# KissCart64-8K-DIP.net
KiCad netlist of a schematic drawn in EAGLE
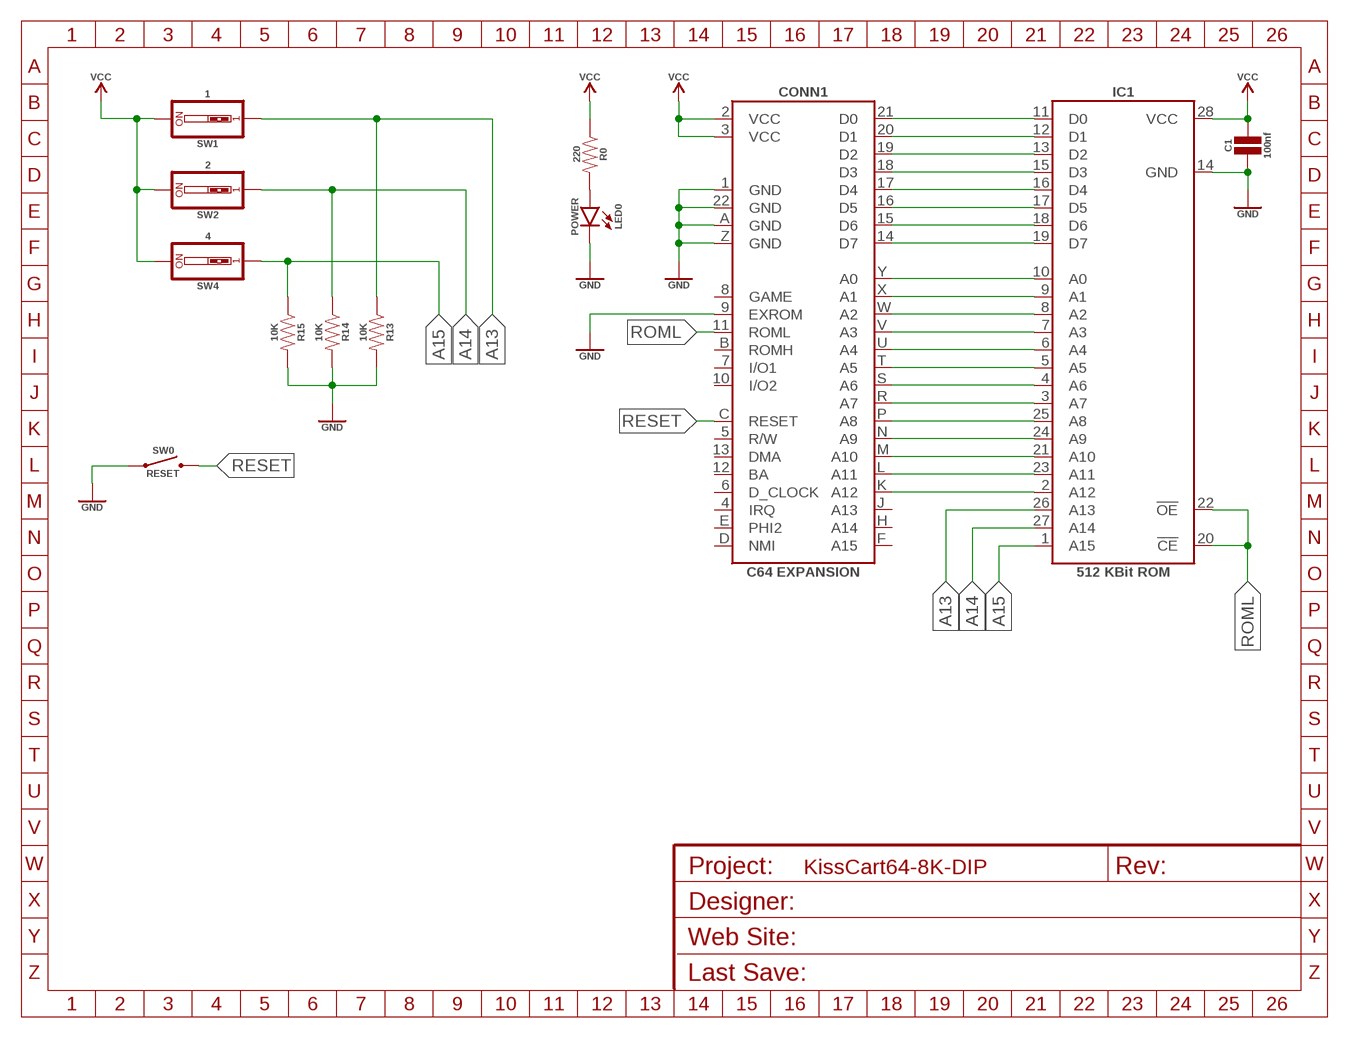
[diagram p0: schematic, sheet 1]

(export (version "E")
  (design (tool "Eeschema 10.0.6"))
  (components
    (comp (ref "C1")
      (value "100nf")
      (footprint "eagle-import:CAPACITOR_CERAMIC_0.2")
      (libsource (lib "eagle-import") (part "CAPACITOR_CERAMIC_0.2"))
    )
    (comp (ref "CONN1")
      (value "C64 EXPANSION")
      (footprint "eagle-import:C64_CARTRIDGE")
      (libsource (lib "eagle-import") (part "C64_CARTDRIGE"))
    )
    (comp (ref "IC1")
      (value "512 KBit ROM")
      (footprint "eagle-import:DIP28W")
      (libsource (lib "eagle-import") (part "27C512_DIP"))
    )
    (comp (ref "LED0")
      (value "POWER")
      (footprint "eagle-import:LED_1206")
      (libsource (lib "eagle-import") (part "LED_NORMAL_1206"))
    )
    (comp (ref "R0")
      (value "220")
      (footprint "eagle-import:RESISTOR_SMT_1206")
      (libsource (lib "eagle-import") (part "RESISTOR_SMT_1206"))
    )
    (comp (ref "R13")
      (value "10K")
      (footprint "eagle-import:RESISTOR_SMT_1206")
      (libsource (lib "eagle-import") (part "RESISTOR_SMT_1206"))
    )
    (comp (ref "R14")
      (value "10K")
      (footprint "eagle-import:RESISTOR_SMT_1206")
      (libsource (lib "eagle-import") (part "RESISTOR_SMT_1206"))
    )
    (comp (ref "R15")
      (value "10K")
      (footprint "eagle-import:RESISTOR_SMT_1206")
      (libsource (lib "eagle-import") (part "RESISTOR_SMT_1206"))
    )
    (comp (ref "SW0")
      (value "RESET")
      (footprint "eagle-import:SWITCH_THT_SIDE")
      (libsource (lib "eagle-import") (part "SWITCH_THT_SIDE"))
    )
    (comp (ref "SW1")
      (value "1")
      (footprint "eagle-import:SWITCH_DIP_01")
      (libsource (lib "eagle-import") (part "SWITCH_DIP_01"))
    )
    (comp (ref "SW2")
      (value "2")
      (footprint "eagle-import:SWITCH_DIP_01")
      (libsource (lib "eagle-import") (part "SWITCH_DIP_01"))
    )
    (comp (ref "SW4")
      (value "4")
      (footprint "eagle-import:SWITCH_DIP_01")
      (libsource (lib "eagle-import") (part "SWITCH_DIP_01"))
    )
  )
  (nets
    (net (code "1") (name "A13") (class "Default")
      (node (ref "IC1") (pin "26") (pinfunction "A13_26") (pintype "input"))
      (node (ref "R13") (pin "1") (pinfunction "1_1") (pintype "passive"))
      (node (ref "SW1") (pin "1") (pinfunction "1_1") (pintype "passive"))
    )
    (net (code "2") (name "A14") (class "Default")
      (node (ref "IC1") (pin "27") (pinfunction "A14_27") (pintype "input"))
      (node (ref "R14") (pin "1") (pinfunction "1_1") (pintype "passive"))
      (node (ref "SW2") (pin "1") (pinfunction "1_1") (pintype "passive"))
    )
    (net (code "3") (name "A15") (class "Default")
      (node (ref "IC1") (pin "1") (pinfunction "A15_1") (pintype "input"))
      (node (ref "R15") (pin "1") (pinfunction "1_1") (pintype "passive"))
      (node (ref "SW4") (pin "1") (pinfunction "1_1") (pintype "passive"))
    )
    (net (code "4") (name "GND") (class "Default")
      (node (ref "C1") (pin "1") (pinfunction "1_1") (pintype "passive"))
      (node (ref "CONN1") (pin "1") (pinfunction "GND_1") (pintype "bidirectional"))
      (node (ref "CONN1") (pin "22") (pinfunction "GND_22") (pintype "bidirectional"))
      (node (ref "CONN1") (pin "9") (pinfunction "EXROM_9") (pintype "bidirectional"))
      (node (ref "CONN1") (pin "A") (pinfunction "GND_A") (pintype "bidirectional"))
      (node (ref "CONN1") (pin "Z") (pinfunction "GND_Z") (pintype "bidirectional"))
      (node (ref "IC1") (pin "14") (pinfunction "GND_14") (pintype "power_in"))
      (node (ref "LED0") (pin "C") (pinfunction "C_C") (pintype "passive"))
      (node (ref "R13") (pin "2") (pinfunction "2_2") (pintype "passive"))
      (node (ref "R14") (pin "2") (pinfunction "2_2") (pintype "passive"))
      (node (ref "R15") (pin "2") (pinfunction "2_2") (pintype "passive"))
      (node (ref "SW0") (pin "1") (pinfunction "1_1") (pintype "passive"))
    )
    (net (code "5") (name "Net-(CONN1-A0)") (class "Default")
      (node (ref "CONN1") (pin "Y") (pinfunction "A0_Y") (pintype "bidirectional"))
      (node (ref "IC1") (pin "10") (pinfunction "A0_10") (pintype "input"))
    )
    (net (code "6") (name "Net-(CONN1-A1)") (class "Default")
      (node (ref "CONN1") (pin "X") (pinfunction "A1_X") (pintype "bidirectional"))
      (node (ref "IC1") (pin "9") (pinfunction "A1_9") (pintype "input"))
    )
    (net (code "7") (name "Net-(CONN1-A2)") (class "Default")
      (node (ref "CONN1") (pin "W") (pinfunction "A2_W") (pintype "bidirectional"))
      (node (ref "IC1") (pin "8") (pinfunction "A2_8") (pintype "input"))
    )
    (net (code "8") (name "Net-(CONN1-A3)") (class "Default")
      (node (ref "CONN1") (pin "V") (pinfunction "A3_V") (pintype "bidirectional"))
      (node (ref "IC1") (pin "7") (pinfunction "A3_7") (pintype "input"))
    )
    (net (code "9") (name "Net-(CONN1-A4)") (class "Default")
      (node (ref "CONN1") (pin "U") (pinfunction "A4_U") (pintype "bidirectional"))
      (node (ref "IC1") (pin "6") (pinfunction "A4_6") (pintype "input"))
    )
    (net (code "10") (name "Net-(CONN1-A5)") (class "Default")
      (node (ref "CONN1") (pin "T") (pinfunction "A5_T") (pintype "bidirectional"))
      (node (ref "IC1") (pin "5") (pinfunction "A5_5") (pintype "input"))
    )
    (net (code "11") (name "Net-(CONN1-A6)") (class "Default")
      (node (ref "CONN1") (pin "S") (pinfunction "A6_S") (pintype "bidirectional"))
      (node (ref "IC1") (pin "4") (pinfunction "A6_4") (pintype "input"))
    )
    (net (code "12") (name "Net-(CONN1-A7)") (class "Default")
      (node (ref "CONN1") (pin "R") (pinfunction "A7_R") (pintype "bidirectional"))
      (node (ref "IC1") (pin "3") (pinfunction "A7_3") (pintype "input"))
    )
    (net (code "13") (name "Net-(CONN1-A8)") (class "Default")
      (node (ref "CONN1") (pin "P") (pinfunction "A8_P") (pintype "bidirectional"))
      (node (ref "IC1") (pin "25") (pinfunction "A8_25") (pintype "input"))
    )
    (net (code "14") (name "Net-(CONN1-A9)") (class "Default")
      (node (ref "CONN1") (pin "N") (pinfunction "A9_N") (pintype "bidirectional"))
      (node (ref "IC1") (pin "24") (pinfunction "A9_24") (pintype "input"))
    )
    (net (code "15") (name "Net-(CONN1-A10)") (class "Default")
      (node (ref "CONN1") (pin "M") (pinfunction "A10_M") (pintype "bidirectional"))
      (node (ref "IC1") (pin "21") (pinfunction "A10_21") (pintype "input"))
    )
    (net (code "16") (name "Net-(CONN1-A11)") (class "Default")
      (node (ref "CONN1") (pin "L") (pinfunction "A11_L") (pintype "bidirectional"))
      (node (ref "IC1") (pin "23") (pinfunction "A11_23") (pintype "input"))
    )
    (net (code "17") (name "Net-(CONN1-A12)") (class "Default")
      (node (ref "CONN1") (pin "K") (pinfunction "A12_K") (pintype "bidirectional"))
      (node (ref "IC1") (pin "2") (pinfunction "A12_2") (pintype "input"))
    )
    (net (code "18") (name "Net-(CONN1-D0)") (class "Default")
      (node (ref "CONN1") (pin "21") (pinfunction "D0_21") (pintype "bidirectional"))
      (node (ref "IC1") (pin "11") (pinfunction "D0_11") (pintype "tri_state"))
    )
    (net (code "19") (name "Net-(CONN1-D1)") (class "Default")
      (node (ref "CONN1") (pin "20") (pinfunction "D1_20") (pintype "bidirectional"))
      (node (ref "IC1") (pin "12") (pinfunction "D1_12") (pintype "tri_state"))
    )
    (net (code "20") (name "Net-(CONN1-D2)") (class "Default")
      (node (ref "CONN1") (pin "19") (pinfunction "D2_19") (pintype "bidirectional"))
      (node (ref "IC1") (pin "13") (pinfunction "D2_13") (pintype "tri_state"))
    )
    (net (code "21") (name "Net-(CONN1-D3)") (class "Default")
      (node (ref "CONN1") (pin "18") (pinfunction "D3_18") (pintype "bidirectional"))
      (node (ref "IC1") (pin "15") (pinfunction "D3_15") (pintype "tri_state"))
    )
    (net (code "22") (name "Net-(CONN1-D4)") (class "Default")
      (node (ref "CONN1") (pin "17") (pinfunction "D4_17") (pintype "bidirectional"))
      (node (ref "IC1") (pin "16") (pinfunction "D4_16") (pintype "tri_state"))
    )
    (net (code "23") (name "Net-(CONN1-D5)") (class "Default")
      (node (ref "CONN1") (pin "16") (pinfunction "D5_16") (pintype "bidirectional"))
      (node (ref "IC1") (pin "17") (pinfunction "D5_17") (pintype "tri_state"))
    )
    (net (code "24") (name "Net-(CONN1-D6)") (class "Default")
      (node (ref "CONN1") (pin "15") (pinfunction "D6_15") (pintype "bidirectional"))
      (node (ref "IC1") (pin "18") (pinfunction "D6_18") (pintype "tri_state"))
    )
    (net (code "25") (name "Net-(CONN1-D7)") (class "Default")
      (node (ref "CONN1") (pin "14") (pinfunction "D7_14") (pintype "bidirectional"))
      (node (ref "IC1") (pin "19") (pinfunction "D7_19") (pintype "tri_state"))
    )
    (net (code "26") (name "Net-(LED0-PadA)") (class "Default")
      (node (ref "LED0") (pin "A") (pinfunction "A_A") (pintype "passive"))
      (node (ref "R0") (pin "2") (pinfunction "2_2") (pintype "passive"))
    )
    (net (code "27") (name "RESET") (class "Default")
      (node (ref "CONN1") (pin "C") (pinfunction "RESET_C") (pintype "bidirectional"))
      (node (ref "SW0") (pin "2") (pinfunction "2_2") (pintype "passive"))
    )
    (net (code "28") (name "ROML") (class "Default")
      (node (ref "CONN1") (pin "11") (pinfunction "ROML_11") (pintype "bidirectional"))
      (node (ref "IC1") (pin "20") (pinfunction "~{CE}_20") (pintype "input"))
      (node (ref "IC1") (pin "22") (pinfunction "~{OE}_22") (pintype "input"))
    )
    (net (code "29") (name "VCC") (class "Default")
      (node (ref "C1") (pin "2") (pinfunction "2_2") (pintype "passive"))
      (node (ref "CONN1") (pin "2") (pinfunction "VCC_2") (pintype "bidirectional"))
      (node (ref "CONN1") (pin "3") (pinfunction "VCC_3") (pintype "bidirectional"))
      (node (ref "IC1") (pin "28") (pinfunction "VCC_28") (pintype "power_in"))
      (node (ref "R0") (pin "1") (pinfunction "1_1") (pintype "passive"))
      (node (ref "SW1") (pin "2") (pinfunction "2_2") (pintype "passive"))
      (node (ref "SW2") (pin "2") (pinfunction "2_2") (pintype "passive"))
      (node (ref "SW4") (pin "2") (pinfunction "2_2") (pintype "passive"))
    )
    (net (code "30") (name "unconnected-(CONN1-A13-PadJ)") (class "Default")
      (node (ref "CONN1") (pin "J") (pinfunction "A13_J") (pintype "bidirectional"))
    )
    (net (code "31") (name "unconnected-(CONN1-A14-PadH)") (class "Default")
      (node (ref "CONN1") (pin "H") (pinfunction "A14_H") (pintype "bidirectional"))
    )
    (net (code "32") (name "unconnected-(CONN1-A15-PadF)") (class "Default")
      (node (ref "CONN1") (pin "F") (pinfunction "A15_F") (pintype "bidirectional"))
    )
    (net (code "33") (name "unconnected-(CONN1-BA-Pad12)") (class "Default")
      (node (ref "CONN1") (pin "12") (pinfunction "BA_12") (pintype "bidirectional"))
    )
    (net (code "34") (name "unconnected-(CONN1-DMA-Pad13)") (class "Default")
      (node (ref "CONN1") (pin "13") (pinfunction "DMA_13") (pintype "bidirectional"))
    )
    (net (code "35") (name "unconnected-(CONN1-D_CLOCK-Pad6)") (class "Default")
      (node (ref "CONN1") (pin "6") (pinfunction "D_CLOCK_6") (pintype "bidirectional"))
    )
    (net (code "36") (name "unconnected-(CONN1-GAME-Pad8)") (class "Default")
      (node (ref "CONN1") (pin "8") (pinfunction "GAME_8") (pintype "bidirectional"))
    )
    (net (code "37") (name "unconnected-(CONN1-IRQ-Pad4)") (class "Default")
      (node (ref "CONN1") (pin "4") (pinfunction "IRQ_4") (pintype "bidirectional"))
    )
    (net (code "38") (name "unconnected-(CONN1-I{slash}O1-Pad7)") (class "Default")
      (node (ref "CONN1") (pin "7") (pinfunction "I/O1_7") (pintype "bidirectional"))
    )
    (net (code "39") (name "unconnected-(CONN1-I{slash}O2-Pad10)") (class "Default")
      (node (ref "CONN1") (pin "10") (pinfunction "I/O2_10") (pintype "bidirectional"))
    )
    (net (code "40") (name "unconnected-(CONN1-NMI-PadD)") (class "Default")
      (node (ref "CONN1") (pin "D") (pinfunction "NMI_D") (pintype "bidirectional"))
    )
    (net (code "41") (name "unconnected-(CONN1-PHI2-PadE)") (class "Default")
      (node (ref "CONN1") (pin "E") (pinfunction "PHI2_E") (pintype "bidirectional"))
    )
    (net (code "42") (name "unconnected-(CONN1-ROMH-PadB)") (class "Default")
      (node (ref "CONN1") (pin "B") (pinfunction "ROMH_B") (pintype "bidirectional"))
    )
    (net (code "43") (name "unconnected-(CONN1-R{slash}W-Pad5)") (class "Default")
      (node (ref "CONN1") (pin "5") (pinfunction "R/W_5") (pintype "bidirectional"))
    )
  )
)
